# Steering.net
KiCad netlist of a schematic drawn in EAGLE
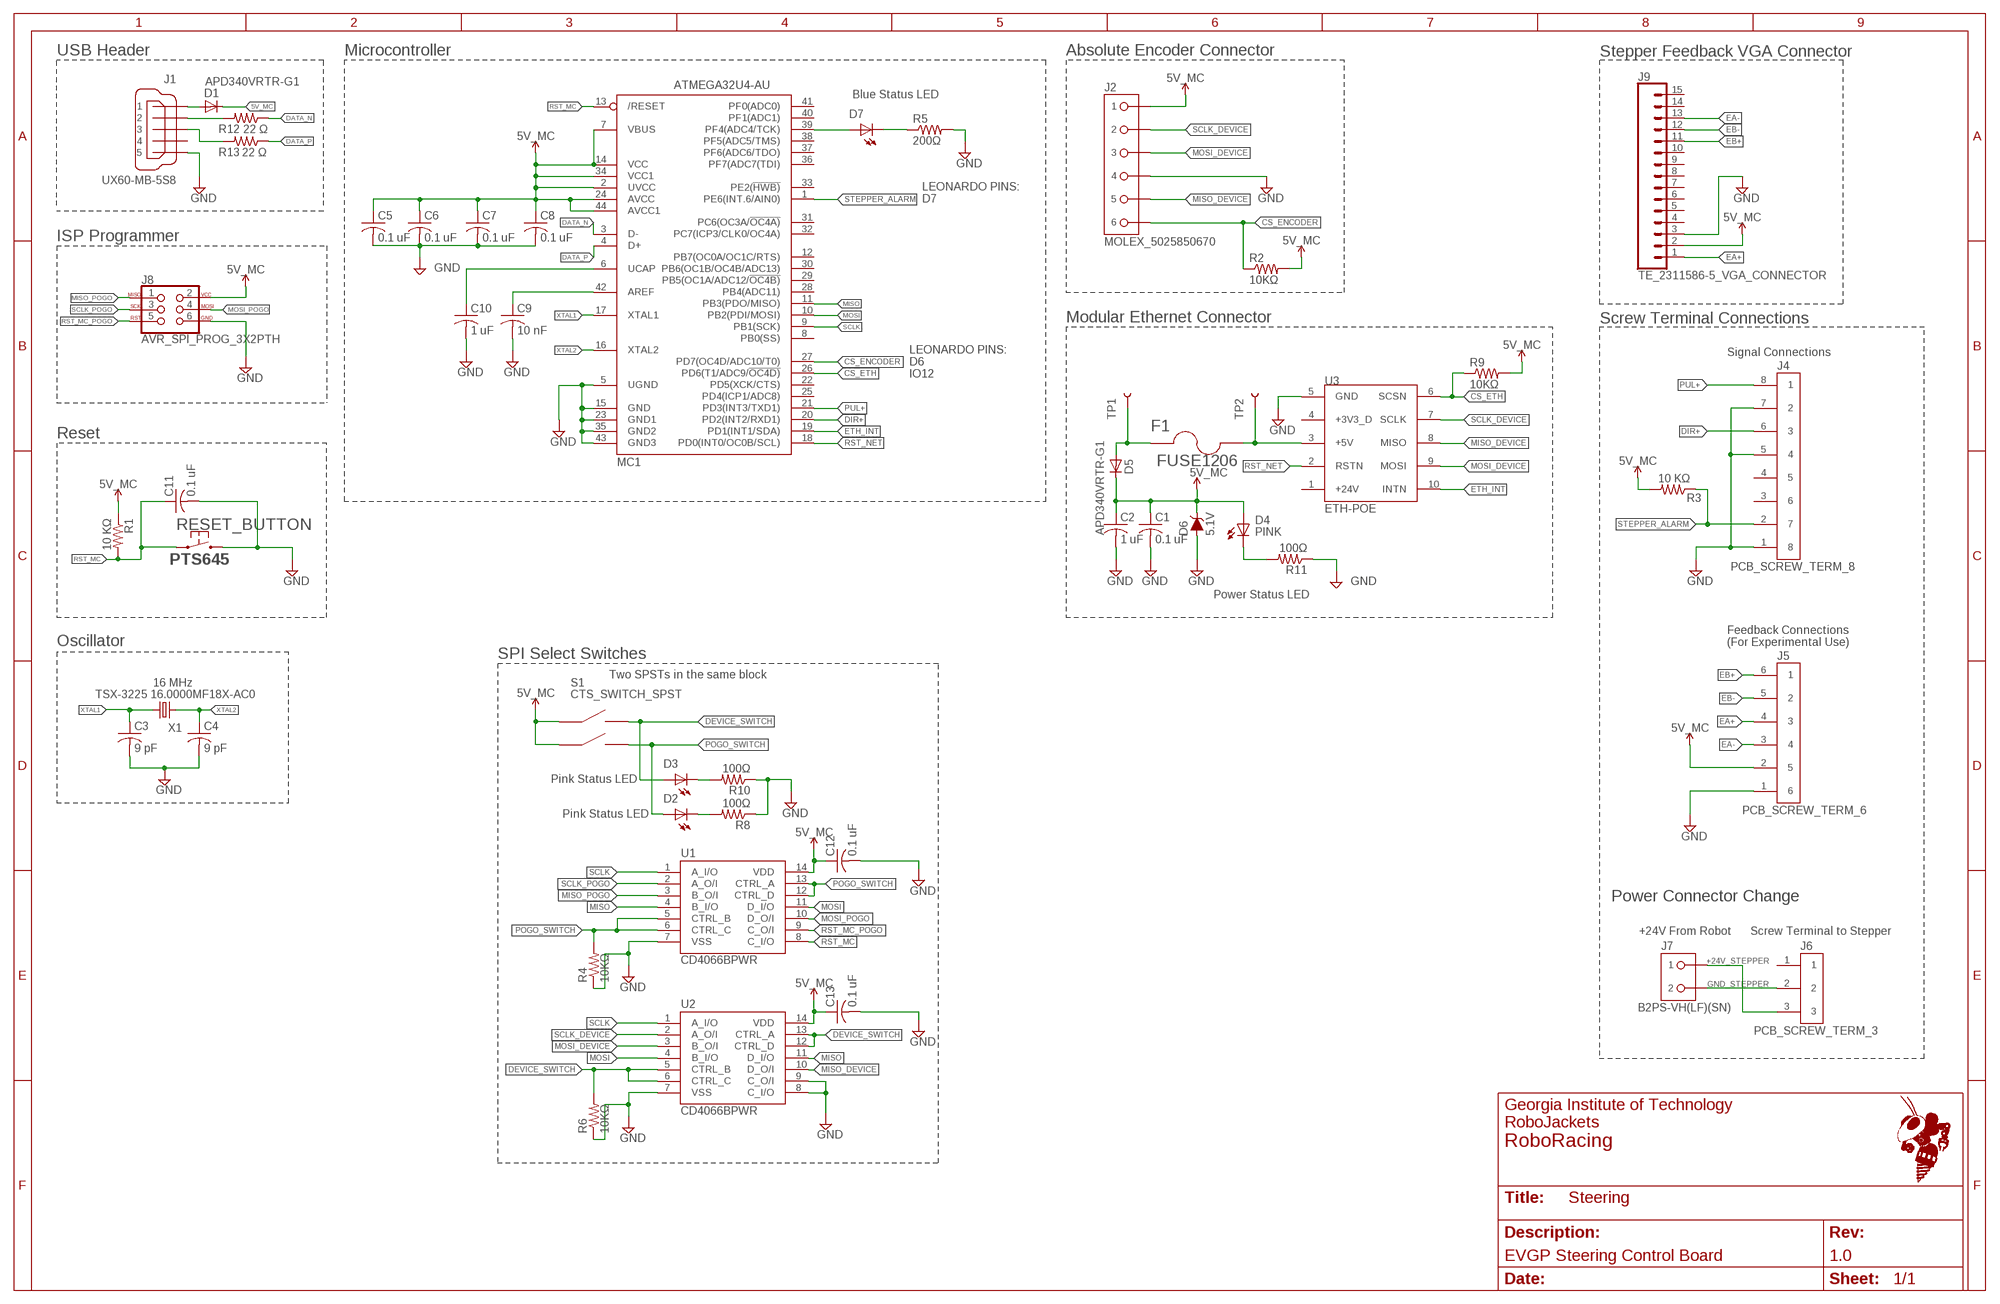
[diagram p0: schematic, sheet 1]

(export (version "E")
  (design (tool "Eeschema 10.0.6"))
  (components
    (comp (ref "C1")
      (value "0.1 uF")
      (footprint "eagle-import:C0603")
      (libsource (lib "eagle-import") (part "C-USC0603"))
    )
    (comp (ref "C2")
      (value "1 uF")
      (footprint "eagle-import:C0603")
      (libsource (lib "eagle-import") (part "C-USC0603"))
    )
    (comp (ref "C3")
      (value "9 pF")
      (footprint "eagle-import:C0603")
      (libsource (lib "eagle-import") (part "C-USC0603"))
    )
    (comp (ref "C4")
      (value "9 pF")
      (footprint "eagle-import:C0603")
      (libsource (lib "eagle-import") (part "C-USC0603"))
    )
    (comp (ref "C5")
      (value "0.1 uF")
      (footprint "eagle-import:C0603")
      (libsource (lib "eagle-import") (part "C-USC0603"))
    )
    (comp (ref "C6")
      (value "0.1 uF")
      (footprint "eagle-import:C0603")
      (libsource (lib "eagle-import") (part "C-USC0603"))
    )
    (comp (ref "C7")
      (value "0.1 uF")
      (footprint "eagle-import:C0603")
      (libsource (lib "eagle-import") (part "C-USC0603"))
    )
    (comp (ref "C8")
      (value "0.1 uF")
      (footprint "eagle-import:C0603")
      (libsource (lib "eagle-import") (part "C-USC0603"))
    )
    (comp (ref "C9")
      (value "10 nF")
      (footprint "eagle-import:C0603")
      (libsource (lib "eagle-import") (part "C-USC0603"))
    )
    (comp (ref "C10")
      (value "1 uF")
      (footprint "eagle-import:C0603")
      (libsource (lib "eagle-import") (part "C-USC0603"))
    )
    (comp (ref "C11")
      (value "0.1 uF")
      (footprint "eagle-import:C0603")
      (libsource (lib "eagle-import") (part "C-USC0603"))
    )
    (comp (ref "C12")
      (value "0.1 uF")
      (footprint "eagle-import:C0603")
      (libsource (lib "eagle-import") (part "C-USC0603"))
    )
    (comp (ref "C13")
      (value "0.1 uF")
      (footprint "eagle-import:C0603")
      (libsource (lib "eagle-import") (part "C-USC0603"))
    )
    (comp (ref "D1")
      (value "APD340VRTR-G1")
      (footprint "eagle-import:DO-214AC")
      (libsource (lib "eagle-import") (part "DIODE-DO-214AC"))
    )
    (comp (ref "D2")
      (value "LED_AA3528VRVCS/A")
      (footprint "eagle-import:KINGBRIGHT_LED")
      (libsource (lib "eagle-import") (part "LED_AA3528VRVCS/A"))
    )
    (comp (ref "D3")
      (value "LED_AA3528VRVCS/A")
      (footprint "eagle-import:KINGBRIGHT_LED")
      (libsource (lib "eagle-import") (part "LED_AA3528VRVCS/A"))
    )
    (comp (ref "D4")
      (value "PINK")
      (footprint "eagle-import:KINGBRIGHT_LED")
      (libsource (lib "eagle-import") (part "LED_AA3528VRVCS/A"))
    )
    (comp (ref "D5")
      (value "APD340VRTR-G1")
      (footprint "eagle-import:DO-214AC")
      (libsource (lib "eagle-import") (part "DIODE-DO-214AC"))
    )
    (comp (ref "D6")
      (value "5.1V")
      (footprint "eagle-import:SOD-323")
      (libsource (lib "eagle-import") (part "DIODE-ZENER-MM3Z3V3T1G"))
    )
    (comp (ref "D7")
      (value "BLUE")
      (footprint "eagle-import:CHIP-LED0603")
      (fields (field (name "MPN") "LTST-C191TBKT"))
      (libsource (lib "eagle-import") (part "LED-SMD-BLUE"))
    )
    (comp (ref "F1")
      (value "FUSE1206")
      (footprint "eagle-import:F1206")
      (libsource (lib "eagle-import") (part "FUSE1206"))
    )
    (comp (ref "J1")
      (value "UX60-MB-5S8")
      (footprint "eagle-import:UX60-MB-5S8")
      (libsource (lib "eagle-import") (part "UX60-MB-5S?8"))
    )
    (comp (ref "J2")
      (value "MOLEX_5025850670")
      (footprint "eagle-import:MOLEX_5025850670")
      (libsource (lib "eagle-import") (part "MOLEX_5025850670"))
    )
    (comp (ref "J4")
      (value "PCB_SCREW_TERM_8")
      (footprint "eagle-import:SCREW_TERMINAL_PCB_CONN_8_POLE")
      (libsource (lib "eagle-import") (part "PCB_SCREW_TERM_8"))
    )
    (comp (ref "J5")
      (value "PCB_SCREW_TERM_6")
      (footprint "eagle-import:SCREW_TERMINAL_PCB_CONN_6_POLE")
      (libsource (lib "eagle-import") (part "PCB_SCREW_TERM_6"))
    )
    (comp (ref "J6")
      (value "PCB_SCREW_TERM_3")
      (footprint "eagle-import:SCREW_TERMINAL_PCB_CONN_3_POLE")
      (libsource (lib "eagle-import") (part "PCB_SCREW_TERM_3"))
    )
    (comp (ref "J7")
      (value "B2PS-VH(LF)(SN)")
      (footprint "eagle-import:B2PS-CENTERED")
      (libsource (lib "eagle-import") (part "B2P?-VH(LF)(SN)S"))
    )
    (comp (ref "J8")
      (value "AVR_SPI_PROG_3X2PTH")
      (footprint "eagle-import:2X3")
      (libsource (lib "eagle-import") (part "AVR_SPI_PROG_3X2PTH"))
    )
    (comp (ref "J9")
      (value "TE_2311586-5_VGA_CONNECTOR")
      (footprint "eagle-import:TE_VGA_2311586-5")
      (libsource (lib "eagle-import") (part "TE_2311586-5_VGA_CONNECTOR"))
    )
    (comp (ref "MC1")
      (value "ATMEGA32U4-AU")
      (footprint "eagle-import:TQFP44")
      (libsource (lib "eagle-import") (part "ATMEGA32U4-AU"))
    )
    (comp (ref "R1")
      (value "10 KΩ")
      (footprint "eagle-import:R0603")
      (libsource (lib "eagle-import") (part "R-US_R0603"))
    )
    (comp (ref "R2")
      (value "10KΩ")
      (footprint "eagle-import:R0603W")
      (libsource (lib "eagle-import") (part "R0603W"))
    )
    (comp (ref "R3")
      (value "10 KΩ")
      (footprint "eagle-import:R0603")
      (libsource (lib "eagle-import") (part "R-US_R0603"))
    )
    (comp (ref "R4")
      (value "10KΩ")
      (footprint "eagle-import:R0603W")
      (libsource (lib "eagle-import") (part "R0603W"))
    )
    (comp (ref "R5")
      (value "200Ω")
      (footprint "eagle-import:R0603W")
      (libsource (lib "eagle-import") (part "R0603W"))
    )
    (comp (ref "R6")
      (value "10KΩ")
      (footprint "eagle-import:R0603W")
      (libsource (lib "eagle-import") (part "R0603W"))
    )
    (comp (ref "R8")
      (value "100Ω")
      (footprint "eagle-import:R0603W")
      (libsource (lib "eagle-import") (part "R0603W"))
    )
    (comp (ref "R9")
      (value "10KΩ")
      (footprint "eagle-import:R0603W")
      (libsource (lib "eagle-import") (part "R0603W"))
    )
    (comp (ref "R10")
      (value "100Ω")
      (footprint "eagle-import:R0603W")
      (libsource (lib "eagle-import") (part "R0603W"))
    )
    (comp (ref "R11")
      (value "100Ω")
      (footprint "eagle-import:R0603W")
      (libsource (lib "eagle-import") (part "R0603W"))
    )
    (comp (ref "R12")
      (value "22 Ω")
      (footprint "eagle-import:R0603")
      (libsource (lib "eagle-import") (part "R-US_R0603"))
    )
    (comp (ref "R13")
      (value "22 Ω")
      (footprint "eagle-import:R0603")
      (libsource (lib "eagle-import") (part "R-US_R0603"))
    )
    (comp (ref "RESET_BUTTON")
      (value "PTS645")
      (footprint "eagle-import:PTS645")
      (libsource (lib "eagle-import") (part "PTS645"))
    )
    (comp (ref "S1")
      (value "CTS_SWITCH_SPST")
      (footprint "eagle-import:CTS_DIP_SWITCH")
      (libsource (lib "eagle-import") (part "CTS_SWITCH_SPST"))
    )
    (comp (ref "TP1")
      (value "TEST-POINTTP_15TH_THRU")
      (footprint "eagle-import:TP_15TH")
      (libsource (lib "eagle-import") (part "TEST-POINTTP_15TH_THRU"))
    )
    (comp (ref "TP2")
      (value "TEST-POINTTP_15TH_THRU")
      (footprint "eagle-import:TP_15TH")
      (libsource (lib "eagle-import") (part "TEST-POINTTP_15TH_THRU"))
    )
    (comp (ref "U1")
      (value "CD4066BPWR")
      (footprint "eagle-import:TSSOP14")
      (libsource (lib "eagle-import") (part "CD4066BPWR"))
    )
    (comp (ref "U2")
      (value "CD4066BPWR")
      (footprint "eagle-import:TSSOP14")
      (libsource (lib "eagle-import") (part "CD4066BPWR"))
    )
    (comp (ref "U3")
      (value "ETH-POE")
      (footprint "eagle-import:HDRVR10W64P4000X254_2X5_1016X508X254B")
      (libsource (lib "eagle-import") (part "ETH-POE"))
    )
    (comp (ref "X1")
      (value "TSX-3225 16.0000MF18X-AC0")
      (footprint "eagle-import:XTAL-3.2X2.5")
      (libsource (lib "eagle-import") (part "XTAL-3.2X2.5"))
    )
  )
  (nets
    (net (code "1") (name "/+24V_STEPPER") (class "Default")
      (node (ref "J6") (pin "3") (pinfunction "3_3") (pintype "bidirectional"))
      (node (ref "J7") (pin "1") (pinfunction "1_1") (pintype "bidirectional"))
    )
    (net (code "2") (name "/GND_STEPPER") (class "Default")
      (node (ref "J6") (pin "2") (pinfunction "2_2") (pintype "bidirectional"))
      (node (ref "J7") (pin "2") (pinfunction "2_2") (pintype "bidirectional"))
    )
    (net (code "3") (name "5V_MC") (class "Default")
      (node (ref "C1") (pin "1") (pinfunction "1_1") (pintype "passive"))
      (node (ref "C12") (pin "1") (pinfunction "1_1") (pintype "passive"))
      (node (ref "C13") (pin "1") (pinfunction "1_1") (pintype "passive"))
      (node (ref "C2") (pin "1") (pinfunction "1_1") (pintype "passive"))
      (node (ref "C5") (pin "1") (pinfunction "1_1") (pintype "passive"))
      (node (ref "C6") (pin "1") (pinfunction "1_1") (pintype "passive"))
      (node (ref "C7") (pin "1") (pinfunction "1_1") (pintype "passive"))
      (node (ref "C8") (pin "1") (pinfunction "1_1") (pintype "passive"))
      (node (ref "D1") (pin "C") (pinfunction "C_C") (pintype "passive"))
      (node (ref "D4") (pin "P$2") (pinfunction "A_P$2") (pintype "passive"))
      (node (ref "D5") (pin "C") (pinfunction "C_C") (pintype "passive"))
      (node (ref "D6") (pin "C") (pinfunction "C_C") (pintype "passive"))
      (node (ref "J2") (pin "1") (pinfunction "1_1") (pintype "passive"))
      (node (ref "J5") (pin "2") (pinfunction "5_2") (pintype "bidirectional"))
      (node (ref "J8") (pin "2") (pinfunction "2_2") (pintype "passive"))
      (node (ref "J9") (pin "2") (pinfunction "2_2") (pintype "passive"))
      (node (ref "MC1") (pin "14") (pinfunction "VCC_14") (pintype "bidirectional"))
      (node (ref "MC1") (pin "2") (pinfunction "UVCC_2") (pintype "bidirectional"))
      (node (ref "MC1") (pin "24") (pinfunction "AVCC_24") (pintype "bidirectional"))
      (node (ref "MC1") (pin "34") (pinfunction "VCC1_34") (pintype "bidirectional"))
      (node (ref "MC1") (pin "44") (pinfunction "AVCC1_44") (pintype "bidirectional"))
      (node (ref "MC1") (pin "7") (pinfunction "VBUS_7") (pintype "bidirectional"))
      (node (ref "R1") (pin "1") (pinfunction "1_1") (pintype "passive"))
      (node (ref "R2") (pin "2") (pinfunction "PIN2_2") (pintype "passive"))
      (node (ref "R3") (pin "2") (pinfunction "2_2") (pintype "passive"))
      (node (ref "R9") (pin "2") (pinfunction "PIN2_2") (pintype "passive"))
      (node (ref "S1") (pin "A2") (pinfunction "COMMON_A2") (pintype "bidirectional"))
      (node (ref "S1") (pin "B2") (pinfunction "COMMON1_B2") (pintype "bidirectional"))
      (node (ref "U1") (pin "14") (pinfunction "VDD_14") (pintype "bidirectional"))
      (node (ref "U2") (pin "14") (pinfunction "VDD_14") (pintype "bidirectional"))
    )
    (net (code "4") (name "CS_ENCODER") (class "Default")
      (node (ref "J2") (pin "6") (pinfunction "6_6") (pintype "passive"))
      (node (ref "MC1") (pin "27") (pinfunction "PD7(OC4D/ADC10/T0)_27") (pintype "bidirectional"))
      (node (ref "R2") (pin "1") (pinfunction "PIN1_1") (pintype "passive"))
    )
    (net (code "5") (name "CS_ETH") (class "Default")
      (node (ref "MC1") (pin "26") (pinfunction "PD6(T1/ADC9/~{OC4D})_26") (pintype "bidirectional"))
      (node (ref "R9") (pin "1") (pinfunction "PIN1_1") (pintype "passive"))
      (node (ref "U3") (pin "6") (pinfunction "SCSN_6") (pintype "bidirectional"))
    )
    (net (code "6") (name "DATA_N") (class "Default")
      (node (ref "MC1") (pin "3") (pinfunction "D-_3") (pintype "bidirectional"))
      (node (ref "R12") (pin "1") (pinfunction "1_1") (pintype "passive"))
    )
    (net (code "7") (name "DATA_P") (class "Default")
      (node (ref "MC1") (pin "4") (pinfunction "D+_4") (pintype "bidirectional"))
      (node (ref "R13") (pin "1") (pinfunction "1_1") (pintype "passive"))
    )
    (net (code "8") (name "DEVICE_SWITCH") (class "Default")
      (node (ref "D3") (pin "P$2") (pinfunction "A_P$2") (pintype "passive"))
      (node (ref "R6") (pin "2") (pinfunction "PIN2_2") (pintype "passive"))
      (node (ref "S1") (pin "A1") (pinfunction "A_A1") (pintype "bidirectional"))
      (node (ref "U2") (pin "12") (pinfunction "CTRL_D_12") (pintype "bidirectional"))
      (node (ref "U2") (pin "13") (pinfunction "CTRL_A_13") (pintype "bidirectional"))
      (node (ref "U2") (pin "5") (pinfunction "CTRL_B_5") (pintype "bidirectional"))
      (node (ref "U2") (pin "6") (pinfunction "CTRL_C_6") (pintype "bidirectional"))
    )
    (net (code "9") (name "DIR+") (class "Default")
      (node (ref "J4") (pin "6") (pinfunction "3_6") (pintype "bidirectional"))
      (node (ref "MC1") (pin "20") (pinfunction "PD2(INT2/RXD1)_20") (pintype "bidirectional"))
    )
    (net (code "10") (name "EA+") (class "Default")
      (node (ref "J5") (pin "4") (pinfunction "3_4") (pintype "bidirectional"))
      (node (ref "J9") (pin "1") (pinfunction "1_1") (pintype "passive"))
    )
    (net (code "11") (name "EA-") (class "Default")
      (node (ref "J5") (pin "3") (pinfunction "4_3") (pintype "bidirectional"))
      (node (ref "J9") (pin "13") (pinfunction "13_13") (pintype "passive"))
    )
    (net (code "12") (name "EB+") (class "Default")
      (node (ref "J5") (pin "6") (pinfunction "1_6") (pintype "bidirectional"))
      (node (ref "J9") (pin "11") (pinfunction "11_11") (pintype "passive"))
    )
    (net (code "13") (name "EB-") (class "Default")
      (node (ref "J5") (pin "5") (pinfunction "2_5") (pintype "bidirectional"))
      (node (ref "J9") (pin "12") (pinfunction "12_12") (pintype "passive"))
    )
    (net (code "14") (name "ETH_INT") (class "Default")
      (node (ref "MC1") (pin "19") (pinfunction "PD1(INT1/SDA)_19") (pintype "bidirectional"))
      (node (ref "U3") (pin "10") (pinfunction "INTN_10") (pintype "bidirectional"))
    )
    (net (code "15") (name "GND") (class "Default")
      (node (ref "C1") (pin "2") (pinfunction "2_2") (pintype "passive"))
      (node (ref "C10") (pin "2") (pinfunction "2_2") (pintype "passive"))
      (node (ref "C11") (pin "2") (pinfunction "2_2") (pintype "passive"))
      (node (ref "C12") (pin "2") (pinfunction "2_2") (pintype "passive"))
      (node (ref "C13") (pin "2") (pinfunction "2_2") (pintype "passive"))
      (node (ref "C2") (pin "2") (pinfunction "2_2") (pintype "passive"))
      (node (ref "C3") (pin "2") (pinfunction "2_2") (pintype "passive"))
      (node (ref "C4") (pin "2") (pinfunction "2_2") (pintype "passive"))
      (node (ref "C5") (pin "2") (pinfunction "2_2") (pintype "passive"))
      (node (ref "C6") (pin "2") (pinfunction "2_2") (pintype "passive"))
      (node (ref "C7") (pin "2") (pinfunction "2_2") (pintype "passive"))
      (node (ref "C8") (pin "2") (pinfunction "2_2") (pintype "passive"))
      (node (ref "C9") (pin "2") (pinfunction "2_2") (pintype "passive"))
      (node (ref "D6") (pin "A") (pinfunction "A_A") (pintype "passive"))
      (node (ref "J1") (pin "5") (pinfunction "5_5") (pintype "passive"))
      (node (ref "J2") (pin "4") (pinfunction "4_4") (pintype "passive"))
      (node (ref "J4") (pin "1") (pinfunction "8_1") (pintype "bidirectional"))
      (node (ref "J4") (pin "5") (pinfunction "4_5") (pintype "bidirectional"))
      (node (ref "J4") (pin "7") (pinfunction "2_7") (pintype "bidirectional"))
      (node (ref "J5") (pin "1") (pinfunction "6_1") (pintype "bidirectional"))
      (node (ref "J8") (pin "6") (pinfunction "6_6") (pintype "passive"))
      (node (ref "J9") (pin "3") (pinfunction "3_3") (pintype "passive"))
      (node (ref "MC1") (pin "15") (pinfunction "GND_15") (pintype "bidirectional"))
      (node (ref "MC1") (pin "23") (pinfunction "GND1_23") (pintype "bidirectional"))
      (node (ref "MC1") (pin "35") (pinfunction "GND2_35") (pintype "bidirectional"))
      (node (ref "MC1") (pin "43") (pinfunction "GND3_43") (pintype "bidirectional"))
      (node (ref "MC1") (pin "5") (pinfunction "UGND_5") (pintype "bidirectional"))
      (node (ref "R10") (pin "1") (pinfunction "PIN1_1") (pintype "passive"))
      (node (ref "R11") (pin "1") (pinfunction "PIN1_1") (pintype "passive"))
      (node (ref "R4") (pin "1") (pinfunction "PIN1_1") (pintype "passive"))
      (node (ref "R5") (pin "2") (pinfunction "PIN2_2") (pintype "passive"))
      (node (ref "R6") (pin "1") (pinfunction "PIN1_1") (pintype "passive"))
      (node (ref "R8") (pin "1") (pinfunction "PIN1_1") (pintype "passive"))
      (node (ref "RESET_BUTTON") (pin "P$3") (pinfunction "2_P$3") (pintype "passive"))
      (node (ref "RESET_BUTTON") (pin "P$4") (pinfunction "2_P$4") (pintype "passive"))
      (node (ref "U1") (pin "7") (pinfunction "VSS_7") (pintype "bidirectional"))
      (node (ref "U2") (pin "7") (pinfunction "VSS_7") (pintype "bidirectional"))
      (node (ref "U2") (pin "8") (pinfunction "C_I/O_8") (pintype "bidirectional"))
      (node (ref "U2") (pin "9") (pinfunction "C_O/I_9") (pintype "bidirectional"))
      (node (ref "U3") (pin "5") (pinfunction "GND_5") (pintype "bidirectional"))
    )
    (net (code "16") (name "MISO") (class "Default")
      (node (ref "MC1") (pin "11") (pinfunction "PB3(PDO/MISO)_11") (pintype "bidirectional"))
      (node (ref "U1") (pin "4") (pinfunction "B_I/O_4") (pintype "bidirectional"))
      (node (ref "U2") (pin "11") (pinfunction "D_I/O_11") (pintype "bidirectional"))
    )
    (net (code "17") (name "MISO_DEVICE") (class "Default")
      (node (ref "J2") (pin "5") (pinfunction "5_5") (pintype "passive"))
      (node (ref "U2") (pin "10") (pinfunction "D_O/I_10") (pintype "bidirectional"))
      (node (ref "U3") (pin "8") (pinfunction "MISO_8") (pintype "bidirectional"))
    )
    (net (code "18") (name "MISO_POGO") (class "Default")
      (node (ref "J8") (pin "1") (pinfunction "1_1") (pintype "passive"))
      (node (ref "U1") (pin "3") (pinfunction "B_O/I_3") (pintype "bidirectional"))
    )
    (net (code "19") (name "MOSI") (class "Default")
      (node (ref "MC1") (pin "10") (pinfunction "PB2(PDI/MOSI)_10") (pintype "bidirectional"))
      (node (ref "U1") (pin "11") (pinfunction "D_I/O_11") (pintype "bidirectional"))
      (node (ref "U2") (pin "4") (pinfunction "B_I/O_4") (pintype "bidirectional"))
    )
    (net (code "20") (name "MOSI_DEVICE") (class "Default")
      (node (ref "J2") (pin "3") (pinfunction "3_3") (pintype "passive"))
      (node (ref "U2") (pin "3") (pinfunction "B_O/I_3") (pintype "bidirectional"))
      (node (ref "U3") (pin "9") (pinfunction "MOSI_9") (pintype "bidirectional"))
    )
    (net (code "21") (name "MOSI_POGO") (class "Default")
      (node (ref "J8") (pin "4") (pinfunction "4_4") (pintype "passive"))
      (node (ref "U1") (pin "10") (pinfunction "D_O/I_10") (pintype "bidirectional"))
    )
    (net (code "22") (name "Net-(D1-PadA)") (class "Default")
      (node (ref "D1") (pin "A") (pinfunction "A_A") (pintype "passive"))
      (node (ref "J1") (pin "1") (pinfunction "1_1") (pintype "passive"))
    )
    (net (code "23") (name "Net-(D2-B)") (class "Default")
      (node (ref "D2") (pin "P$1") (pinfunction "B_P$1") (pintype "passive"))
      (node (ref "R8") (pin "2") (pinfunction "PIN2_2") (pintype "passive"))
    )
    (net (code "24") (name "Net-(D3-B)") (class "Default")
      (node (ref "D3") (pin "P$1") (pinfunction "B_P$1") (pintype "passive"))
      (node (ref "R10") (pin "2") (pinfunction "PIN2_2") (pintype "passive"))
    )
    (net (code "25") (name "Net-(D4-B)") (class "Default")
      (node (ref "D4") (pin "P$1") (pinfunction "B_P$1") (pintype "passive"))
      (node (ref "R11") (pin "2") (pinfunction "PIN2_2") (pintype "passive"))
    )
    (net (code "26") (name "Net-(D7-K)") (class "Default")
      (node (ref "D7") (pin "C") (pinfunction "K_C") (pintype "passive"))
      (node (ref "R5") (pin "1") (pinfunction "PIN1_1") (pintype "passive"))
    )
    (net (code "27") (name "Net-(J1-Pad2)") (class "Default")
      (node (ref "J1") (pin "2") (pinfunction "2_2") (pintype "passive"))
      (node (ref "R12") (pin "2") (pinfunction "2_2") (pintype "passive"))
    )
    (net (code "28") (name "Net-(J1-Pad3)") (class "Default")
      (node (ref "J1") (pin "3") (pinfunction "3_3") (pintype "passive"))
      (node (ref "R13") (pin "2") (pinfunction "2_2") (pintype "passive"))
    )
    (net (code "29") (name "Net-(MC1-AREF)") (class "Default")
      (node (ref "C9") (pin "1") (pinfunction "1_1") (pintype "passive"))
      (node (ref "MC1") (pin "42") (pinfunction "AREF_42") (pintype "bidirectional"))
    )
    (net (code "30") (name "Net-(MC1-PF4(ADC4{slash}TCK))") (class "Default")
      (node (ref "D7") (pin "A") (pinfunction "A_A") (pintype "passive"))
      (node (ref "MC1") (pin "39") (pinfunction "PF4(ADC4/TCK)_39") (pintype "bidirectional"))
    )
    (net (code "31") (name "Net-(MC1-UCAP)") (class "Default")
      (node (ref "C10") (pin "1") (pinfunction "1_1") (pintype "passive"))
      (node (ref "MC1") (pin "6") (pinfunction "UCAP_6") (pintype "bidirectional"))
    )
    (net (code "32") (name "Net-(TP1-1)") (class "Default")
      (node (ref "D5") (pin "A") (pinfunction "A_A") (pintype "passive"))
      (node (ref "F1") (pin "1") (pinfunction "1_1") (pintype "passive"))
      (node (ref "TP1") (pin "P$1") (pinfunction "1_P$1") (pintype "bidirectional"))
    )
    (net (code "33") (name "Net-(TP2-1)") (class "Default")
      (node (ref "F1") (pin "2") (pinfunction "2_2") (pintype "passive"))
      (node (ref "TP2") (pin "P$1") (pinfunction "1_P$1") (pintype "bidirectional"))
      (node (ref "U3") (pin "3") (pinfunction "+5V_3") (pintype "bidirectional"))
    )
    (net (code "34") (name "POGO_SWITCH") (class "Default")
      (node (ref "D2") (pin "P$2") (pinfunction "A_P$2") (pintype "passive"))
      (node (ref "R4") (pin "2") (pinfunction "PIN2_2") (pintype "passive"))
      (node (ref "S1") (pin "B1") (pinfunction "A1_B1") (pintype "bidirectional"))
      (node (ref "U1") (pin "12") (pinfunction "CTRL_D_12") (pintype "bidirectional"))
      (node (ref "U1") (pin "13") (pinfunction "CTRL_A_13") (pintype "bidirectional"))
      (node (ref "U1") (pin "5") (pinfunction "CTRL_B_5") (pintype "bidirectional"))
      (node (ref "U1") (pin "6") (pinfunction "CTRL_C_6") (pintype "bidirectional"))
    )
    (net (code "35") (name "PUL+") (class "Default")
      (node (ref "J4") (pin "8") (pinfunction "1_8") (pintype "bidirectional"))
      (node (ref "MC1") (pin "21") (pinfunction "PD3(INT3/TXD1)_21") (pintype "bidirectional"))
    )
    (net (code "36") (name "RST_MC") (class "Default")
      (node (ref "C11") (pin "1") (pinfunction "1_1") (pintype "passive"))
      (node (ref "MC1") (pin "13") (pinfunction "/RESET_13") (pintype "bidirectional"))
      (node (ref "R1") (pin "2") (pinfunction "2_2") (pintype "passive"))
      (node (ref "RESET_BUTTON") (pin "P$1") (pinfunction "1_P$1") (pintype "passive"))
      (node (ref "RESET_BUTTON") (pin "P$2") (pinfunction "1_P$2") (pintype "passive"))
      (node (ref "U1") (pin "8") (pinfunction "C_I/O_8") (pintype "bidirectional"))
    )
    (net (code "37") (name "RST_MC_POGO") (class "Default")
      (node (ref "J8") (pin "5") (pinfunction "5_5") (pintype "passive"))
      (node (ref "U1") (pin "9") (pinfunction "C_O/I_9") (pintype "bidirectional"))
    )
    (net (code "38") (name "RST_NET") (class "Default")
      (node (ref "MC1") (pin "18") (pinfunction "PD0(INT0/OC0B/SCL)_18") (pintype "bidirectional"))
      (node (ref "U3") (pin "2") (pinfunction "RSTN_2") (pintype "bidirectional"))
    )
    (net (code "39") (name "SCLK") (class "Default")
      (node (ref "MC1") (pin "9") (pinfunction "PB1(SCK)_9") (pintype "bidirectional"))
      (node (ref "U1") (pin "1") (pinfunction "A_I/O_1") (pintype "bidirectional"))
      (node (ref "U2") (pin "1") (pinfunction "A_I/O_1") (pintype "bidirectional"))
    )
    (net (code "40") (name "SCLK_DEVICE") (class "Default")
      (node (ref "J2") (pin "2") (pinfunction "2_2") (pintype "passive"))
      (node (ref "U2") (pin "2") (pinfunction "A_O/I_2") (pintype "bidirectional"))
      (node (ref "U3") (pin "7") (pinfunction "SCLK_7") (pintype "bidirectional"))
    )
    (net (code "41") (name "SCLK_POGO") (class "Default")
      (node (ref "J8") (pin "3") (pinfunction "3_3") (pintype "passive"))
      (node (ref "U1") (pin "2") (pinfunction "A_O/I_2") (pintype "bidirectional"))
    )
    (net (code "42") (name "STEPPER_ALARM") (class "Default")
      (node (ref "J4") (pin "2") (pinfunction "7_2") (pintype "bidirectional"))
      (node (ref "MC1") (pin "1") (pinfunction "PE6(INT.6/AIN0)_1") (pintype "bidirectional"))
      (node (ref "R3") (pin "1") (pinfunction "1_1") (pintype "passive"))
    )
    (net (code "43") (name "XTAL1") (class "Default")
      (node (ref "C3") (pin "1") (pinfunction "1_1") (pintype "passive"))
      (node (ref "MC1") (pin "17") (pinfunction "XTAL1_17") (pintype "bidirectional"))
      (node (ref "X1") (pin "1") (pinfunction "1_1") (pintype "passive"))
    )
    (net (code "44") (name "XTAL2") (class "Default")
      (node (ref "C4") (pin "1") (pinfunction "1_1") (pintype "passive"))
      (node (ref "MC1") (pin "16") (pinfunction "XTAL2_16") (pintype "bidirectional"))
      (node (ref "X1") (pin "3") (pinfunction "2_3") (pintype "passive"))
    )
    (net (code "45") (name "unconnected-(J1-Pad4)") (class "Default")
      (node (ref "J1") (pin "4") (pinfunction "4_4") (pintype "passive"))
    )
    (net (code "46") (name "unconnected-(J4-5-Pad4)") (class "Default")
      (node (ref "J4") (pin "4") (pinfunction "5_4") (pintype "bidirectional"))
    )
    (net (code "47") (name "unconnected-(J4-6-Pad3)") (class "Default")
      (node (ref "J4") (pin "3") (pinfunction "6_3") (pintype "bidirectional"))
    )
    (net (code "48") (name "unconnected-(J6-Pad1)") (class "Default")
      (node (ref "J6") (pin "1") (pinfunction "1_1") (pintype "bidirectional"))
    )
    (net (code "49") (name "unconnected-(J9-Pad4)") (class "Default")
      (node (ref "J9") (pin "4") (pinfunction "4_4") (pintype "passive"))
    )
    (net (code "50") (name "unconnected-(J9-Pad5)") (class "Default")
      (node (ref "J9") (pin "5") (pinfunction "5_5") (pintype "passive"))
    )
    (net (code "51") (name "unconnected-(J9-Pad6)") (class "Default")
      (node (ref "J9") (pin "6") (pinfunction "6_6") (pintype "passive"))
    )
    (net (code "52") (name "unconnected-(J9-Pad7)") (class "Default")
      (node (ref "J9") (pin "7") (pinfunction "7_7") (pintype "passive"))
    )
    (net (code "53") (name "unconnected-(J9-Pad8)") (class "Default")
      (node (ref "J9") (pin "8") (pinfunction "8_8") (pintype "passive"))
    )
    (net (code "54") (name "unconnected-(J9-Pad9)") (class "Default")
      (node (ref "J9") (pin "9") (pinfunction "9_9") (pintype "passive"))
    )
    (net (code "55") (name "unconnected-(J9-Pad10)") (class "Default")
      (node (ref "J9") (pin "10") (pinfunction "10_10") (pintype "passive"))
    )
    (net (code "56") (name "unconnected-(J9-Pad14)") (class "Default")
      (node (ref "J9") (pin "14") (pinfunction "14_14") (pintype "passive"))
    )
    (net (code "57") (name "unconnected-(J9-Pad15)") (class "Default")
      (node (ref "J9") (pin "15") (pinfunction "15_15") (pintype "passive"))
    )
    (net (code "58") (name "unconnected-(MC1-PB0(SS)-Pad8)") (class "Default")
      (node (ref "MC1") (pin "8") (pinfunction "PB0(SS)_8") (pintype "bidirectional"))
    )
    (net (code "59") (name "unconnected-(MC1-PB4(ADC11)-Pad28)") (class "Default")
      (node (ref "MC1") (pin "28") (pinfunction "PB4(ADC11)_28") (pintype "bidirectional"))
    )
    (net (code "60") (name "unconnected-(MC1-PB5(OC1A{slash}ADC12{slash}~{OC4B})-Pad29)") (class "Default")
      (node (ref "MC1") (pin "29") (pinfunction "PB5(OC1A/ADC12/~{OC4B})_29") (pintype "bidirectional"))
    )
    (net (code "61") (name "unconnected-(MC1-PB6(OC1B{slash}OC4B{slash}ADC13)-Pad30)") (class "Default")
      (node (ref "MC1") (pin "30") (pinfunction "PB6(OC1B/OC4B/ADC13)_30") (pintype "bidirectional"))
    )
    (net (code "62") (name "unconnected-(MC1-PB7(OC0A{slash}OC1C{slash}RTS)-Pad12)") (class "Default")
      (node (ref "MC1") (pin "12") (pinfunction "PB7(OC0A/OC1C/RTS)_12") (pintype "bidirectional"))
    )
    (net (code "63") (name "unconnected-(MC1-PC6(OC3A{slash}~{OC4A})-Pad31)") (class "Default")
      (node (ref "MC1") (pin "31") (pinfunction "PC6(OC3A/~{OC4A})_31") (pintype "bidirectional"))
    )
    (net (code "64") (name "unconnected-(MC1-PC7(ICP3{slash}CLK0{slash}OC4A)-Pad32)") (class "Default")
      (node (ref "MC1") (pin "32") (pinfunction "PC7(ICP3/CLK0/OC4A)_32") (pintype "bidirectional"))
    )
    (net (code "65") (name "unconnected-(MC1-PD4(ICP1{slash}ADC8)-Pad25)") (class "Default")
      (node (ref "MC1") (pin "25") (pinfunction "PD4(ICP1/ADC8)_25") (pintype "bidirectional"))
    )
    (net (code "66") (name "unconnected-(MC1-PD5(XCK{slash}CTS)-Pad22)") (class "Default")
      (node (ref "MC1") (pin "22") (pinfunction "PD5(XCK/CTS)_22") (pintype "bidirectional"))
    )
    (net (code "67") (name "unconnected-(MC1-PE2(~{HWB})-Pad33)") (class "Default")
      (node (ref "MC1") (pin "33") (pinfunction "PE2(~{HWB})_33") (pintype "bidirectional"))
    )
    (net (code "68") (name "unconnected-(MC1-PF0(ADC0)-Pad41)") (class "Default")
      (node (ref "MC1") (pin "41") (pinfunction "PF0(ADC0)_41") (pintype "bidirectional"))
    )
    (net (code "69") (name "unconnected-(MC1-PF1(ADC1)-Pad40)") (class "Default")
      (node (ref "MC1") (pin "40") (pinfunction "PF1(ADC1)_40") (pintype "bidirectional"))
    )
    (net (code "70") (name "unconnected-(MC1-PF5(ADC5{slash}TMS)-Pad38)") (class "Default")
      (node (ref "MC1") (pin "38") (pinfunction "PF5(ADC5/TMS)_38") (pintype "bidirectional"))
    )
    (net (code "71") (name "unconnected-(MC1-PF6(ADC6{slash}TDO)-Pad37)") (class "Default")
      (node (ref "MC1") (pin "37") (pinfunction "PF6(ADC6/TDO)_37") (pintype "bidirectional"))
    )
    (net (code "72") (name "unconnected-(MC1-PF7(ADC7(TDI)-Pad36)") (class "Default")
      (node (ref "MC1") (pin "36") (pinfunction "PF7(ADC7(TDI)_36") (pintype "bidirectional"))
    )
    (net (code "73") (name "unconnected-(U3-+3V3_D-Pad4)") (class "Default")
      (node (ref "U3") (pin "4") (pinfunction "+3V3_D_4") (pintype "bidirectional"))
    )
    (net (code "74") (name "unconnected-(U3-+24V-Pad1)") (class "Default")
      (node (ref "U3") (pin "1") (pinfunction "+24V_1") (pintype "bidirectional"))
    )
  )
)
